# PUTTY.net
KiCad netlist of a schematic drawn in Altium Designer
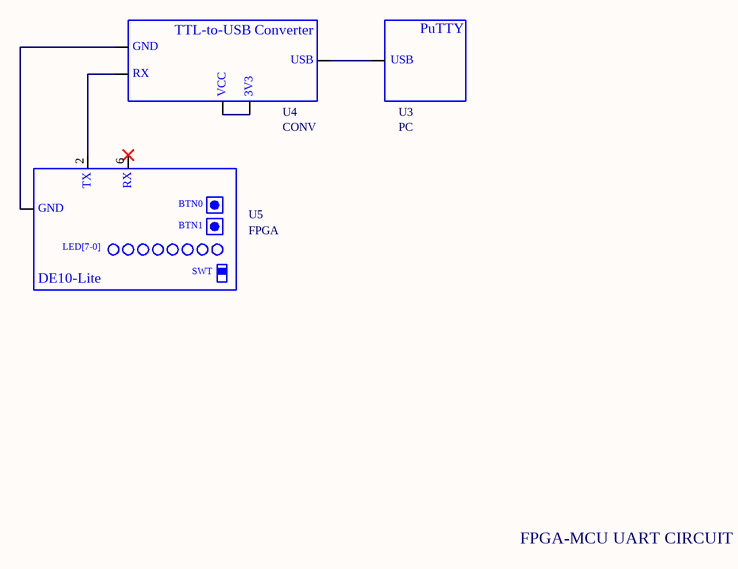
[diagram p0: PUTTY.SchDoc]

(export (version "E")
  (design (tool "Eeschema 10.0.6"))
  (components
    (comp (ref "U3") (value "PC") (libsource (lib "UART") (part "PC")))
    (comp (ref "U4") (value "CONV") (libsource (lib "UART") (part "TTL2USB")))
    (comp (ref "U5") (value "FPGA") (libsource (lib "UART") (part "FPGA")))
  )
  (nets
    (net (code "1") (name "Net-(U4-15)") (class "Default")
      (node (ref "U3") (pin "0") (pinfunction "0_0") (pintype "passive"))
      (node (ref "U4") (pin "1") (pinfunction "15_1") (pintype "passive"))
    )
    (net (code "2") (name "Net-(U4-Pad0)") (class "Default")
      (node (ref "U4") (pin "0") (pinfunction "0_0") (pintype "passive"))
      (node (ref "U5") (pin "3") (pinfunction "3_3") (pintype "passive"))
    )
    (net (code "3") (name "Net-(U4-Pad11)") (class "Default")
      (node (ref "U4") (pin "11") (pinfunction "11_11") (pintype "passive"))
      (node (ref "U4") (pin "12") (pinfunction "12_12") (pintype "passive"))
    )
    (net (code "4") (name "Net-(U4-Pad16)") (class "Default")
      (node (ref "U4") (pin "16") (pinfunction "16_16") (pintype "passive"))
      (node (ref "U5") (pin "2") (pinfunction "2_2") (pintype "passive"))
    )
    (net (code "5") (name "unconnected-(U5-Pad6)") (class "Default")
      (node (ref "U5") (pin "6") (pinfunction "6_6") (pintype "passive+no_connect"))
    )
  )
)
